# Ladder_ATTN.net
KiCad netlist of a schematic drawn in Altium Designer
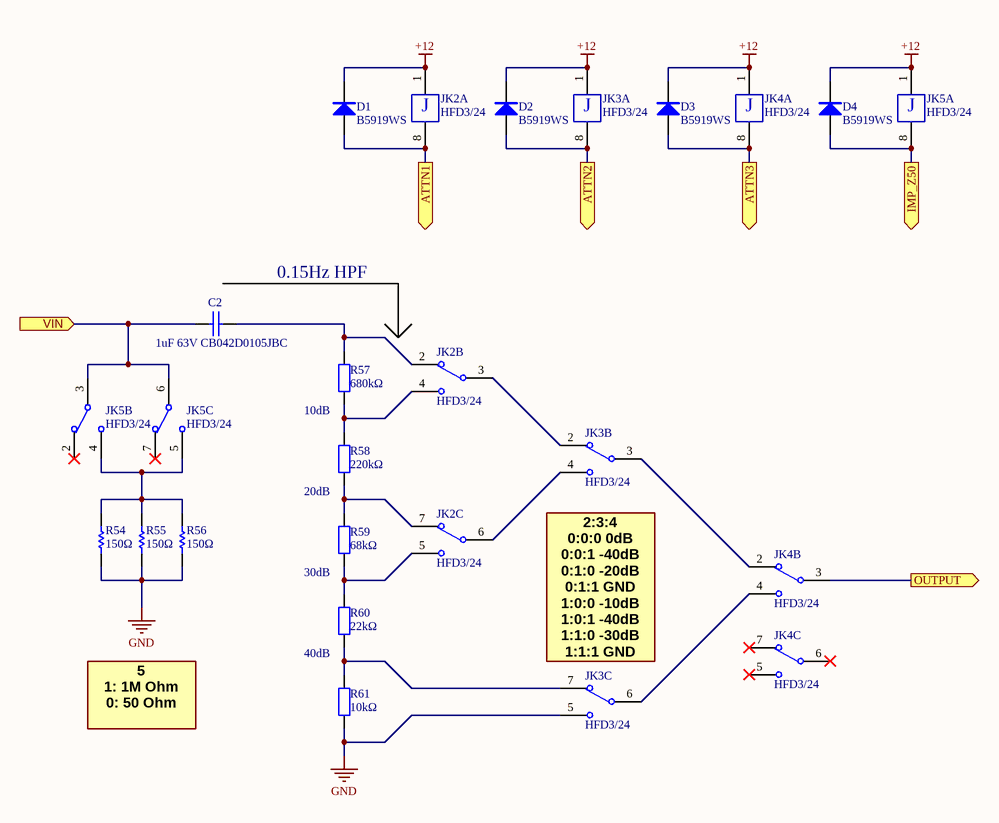
[diagram p0: Ladder_ATTN.SchDoc]

(export (version "E")
  (design (tool "Eeschema 10.0.6"))
  (components
    (comp (ref "C2")
      (value "1uF 63V CB042D0105JBC")
      (footprint "2225C")
      (description "无极性电容")
      (libsource (lib "电容") (part "CAP"))
    )
    (comp (ref "D1")
      (value "B5919WS")
      (footprint "SOD-323")
      (description "肖特基二极管")
      (fields (field (name "版权归属") "源创客"))
      (libsource (lib "源创客") (part "1N5819"))
    )
    (comp (ref "D2")
      (value "B5919WS")
      (footprint "SOD-323")
      (description "肖特基二极管")
      (fields (field (name "版权归属") "源创客"))
      (libsource (lib "源创客") (part "1N5819"))
    )
    (comp (ref "D3")
      (value "B5919WS")
      (footprint "SOD-323")
      (description "肖特基二极管")
      (fields (field (name "版权归属") "源创客"))
      (libsource (lib "源创客") (part "1N5819"))
    )
    (comp (ref "D4")
      (value "B5919WS")
      (footprint "SOD-323")
      (description "肖特基二极管")
      (fields (field (name "版权归属") "源创客"))
      (libsource (lib "源创客") (part "1N5819"))
    )
    (comp (ref "JK2")
      (value "HFD3/24")
      (footprint "HFD3-DIP")
      (description "超小型两组转换")
      (fields (field (name "版权归属") "源创客"))
      (libsource (lib "") (part "HFD3_1"))
    )
    (comp (ref "JK3")
      (value "HFD3/24")
      (footprint "HFD3-DIP")
      (description "超小型两组转换")
      (fields (field (name "版权归属") "源创客"))
      (libsource (lib "") (part "HFD3_2"))
    )
    (comp (ref "JK4")
      (value "HFD3/24")
      (footprint "HFD3-DIP")
      (description "超小型两组转换")
      (fields (field (name "版权归属") "源创客"))
      (libsource (lib "继电器") (part "HFD3"))
    )
    (comp (ref "JK5")
      (value "HFD3/24")
      (footprint "HFD3-DIP")
      (description "超小型两组转换")
      (fields (field (name "版权归属") "源创客"))
      (libsource (lib "") (part "HFD3_4"))
    )
    (comp (ref "R54") (value "150Ω") (footprint "2512R") (libsource (lib "电阻") (part "RES")))
    (comp (ref "R55") (value "150Ω") (footprint "2512R") (libsource (lib "电阻") (part "RES")))
    (comp (ref "R56") (value "150Ω") (footprint "2512R") (libsource (lib "电阻") (part "RES")))
    (comp (ref "R57")
      (value "680kΩ")
      (footprint "0603_R")
      (description "贴片电阻")
      (libsource (lib "Miscellaneous Devices LC") (part "0603 680KΩ (6803) 1%"))
    )
    (comp (ref "R58")
      (value "220kΩ")
      (footprint "0603_R")
      (description "贴片电阻")
      (libsource (lib "Miscellaneous Devices LC") (part "0603 220KΩ (2203) 1%"))
    )
    (comp (ref "R59")
      (value "68kΩ")
      (footprint "0603_R")
      (description "贴片电阻")
      (libsource (lib "Miscellaneous Devices LC") (part "0603 680KΩ (6803) 1%"))
    )
    (comp (ref "R60")
      (value "22kΩ")
      (footprint "0603_R")
      (description "贴片电阻")
      (libsource (lib "Miscellaneous Devices LC") (part "0603 220KΩ (2203) 1%"))
    )
    (comp (ref "R61")
      (value "10kΩ")
      (footprint "0603_R")
      (description "贴片电阻")
      (libsource (lib "Miscellaneous Devices LC") (part "0603 220KΩ (2203) 1%"))
    )
  )
  (nets
    (net (code "1") (name "+12") (class "Default")
      (node (ref "D1") (pin "2") (pinfunction "K_2") (pintype "passive"))
      (node (ref "D2") (pin "2") (pinfunction "K_2") (pintype "passive"))
      (node (ref "D3") (pin "2") (pinfunction "K_2") (pintype "passive"))
      (node (ref "D4") (pin "2") (pinfunction "K_2") (pintype "passive"))
      (node (ref "JK2") (pin "1") (pinfunction "1_1") (pintype "passive"))
      (node (ref "JK3") (pin "1") (pinfunction "1_1") (pintype "passive"))
      (node (ref "JK4") (pin "1") (pinfunction "1_1") (pintype "passive"))
      (node (ref "JK5") (pin "1") (pinfunction "1_1") (pintype "passive"))
    )
    (net (code "2") (name "/ATTN1") (class "Default")
      (node (ref "D1") (pin "1") (pinfunction "A_1") (pintype "passive"))
      (node (ref "JK2") (pin "8") (pinfunction "8_8") (pintype "passive"))
    )
    (net (code "3") (name "/ATTN2") (class "Default")
      (node (ref "D2") (pin "1") (pinfunction "A_1") (pintype "passive"))
      (node (ref "JK3") (pin "8") (pinfunction "8_8") (pintype "passive"))
    )
    (net (code "4") (name "/ATTN3") (class "Default")
      (node (ref "D3") (pin "1") (pinfunction "A_1") (pintype "passive"))
      (node (ref "JK4") (pin "8") (pinfunction "8_8") (pintype "passive"))
    )
    (net (code "5") (name "/IMP_Z50") (class "Default")
      (node (ref "D4") (pin "1") (pinfunction "A_1") (pintype "passive"))
      (node (ref "JK5") (pin "8") (pinfunction "8_8") (pintype "passive"))
    )
    (net (code "6") (name "/OUTPUT") (class "Default")
      (node (ref "JK4") (pin "3") (pinfunction "3_3") (pintype "passive"))
    )
    (net (code "7") (name "/VIN") (class "Default")
      (node (ref "C2") (pin "1") (pinfunction "1_1") (pintype "passive"))
      (node (ref "JK5") (pin "3") (pinfunction "3_3") (pintype "passive"))
      (node (ref "JK5") (pin "6") (pinfunction "6_6") (pintype "passive"))
    )
    (net (code "8") (name "GND") (class "Default")
      (node (ref "JK3") (pin "5") (pinfunction "5_5") (pintype "passive"))
      (node (ref "R54") (pin "1") (pinfunction "1_1") (pintype "passive"))
      (node (ref "R55") (pin "1") (pinfunction "1_1") (pintype "passive"))
      (node (ref "R56") (pin "1") (pinfunction "1_1") (pintype "passive"))
      (node (ref "R61") (pin "1") (pinfunction "1_1") (pintype "passive"))
    )
    (net (code "9") (name "Net-(C2-Pad2)") (class "Default")
      (node (ref "C2") (pin "2") (pinfunction "2_2") (pintype "passive"))
      (node (ref "JK2") (pin "2") (pinfunction "2_2") (pintype "passive"))
      (node (ref "R57") (pin "2") (pinfunction "2_2") (pintype "passive"))
    )
    (net (code "10") (name "Net-(JK2-Pad3)") (class "Default")
      (node (ref "JK2") (pin "3") (pinfunction "3_3") (pintype "passive"))
      (node (ref "JK3") (pin "2") (pinfunction "2_2") (pintype "passive"))
    )
    (net (code "11") (name "Net-(JK2-Pad4)") (class "Default")
      (node (ref "JK2") (pin "4") (pinfunction "4_4") (pintype "passive"))
      (node (ref "R57") (pin "1") (pinfunction "1_1") (pintype "passive"))
      (node (ref "R58") (pin "2") (pinfunction "2_2") (pintype "passive"))
    )
    (net (code "12") (name "Net-(JK2-Pad5)") (class "Default")
      (node (ref "JK2") (pin "5") (pinfunction "5_5") (pintype "passive"))
      (node (ref "R59") (pin "1") (pinfunction "1_1") (pintype "passive"))
      (node (ref "R60") (pin "2") (pinfunction "2_2") (pintype "passive"))
    )
    (net (code "13") (name "Net-(JK2-Pad6)") (class "Default")
      (node (ref "JK2") (pin "6") (pinfunction "6_6") (pintype "passive"))
      (node (ref "JK3") (pin "4") (pinfunction "4_4") (pintype "passive"))
    )
    (net (code "14") (name "Net-(JK2-Pad7)") (class "Default")
      (node (ref "JK2") (pin "7") (pinfunction "7_7") (pintype "passive"))
      (node (ref "R58") (pin "1") (pinfunction "1_1") (pintype "passive"))
      (node (ref "R59") (pin "2") (pinfunction "2_2") (pintype "passive"))
    )
    (net (code "15") (name "Net-(JK3-Pad3)") (class "Default")
      (node (ref "JK3") (pin "3") (pinfunction "3_3") (pintype "passive"))
      (node (ref "JK4") (pin "2") (pinfunction "2_2") (pintype "passive"))
    )
    (net (code "16") (name "Net-(JK3-Pad6)") (class "Default")
      (node (ref "JK3") (pin "6") (pinfunction "6_6") (pintype "passive"))
      (node (ref "JK4") (pin "4") (pinfunction "4_4") (pintype "passive"))
    )
    (net (code "17") (name "Net-(JK3-Pad7)") (class "Default")
      (node (ref "JK3") (pin "7") (pinfunction "7_7") (pintype "passive"))
      (node (ref "R60") (pin "1") (pinfunction "1_1") (pintype "passive"))
      (node (ref "R61") (pin "2") (pinfunction "2_2") (pintype "passive"))
    )
    (net (code "18") (name "Net-(JK5-Pad4)") (class "Default")
      (node (ref "JK5") (pin "4") (pinfunction "4_4") (pintype "passive"))
      (node (ref "JK5") (pin "5") (pinfunction "5_5") (pintype "passive"))
      (node (ref "R54") (pin "2") (pinfunction "2_2") (pintype "passive"))
      (node (ref "R55") (pin "2") (pinfunction "2_2") (pintype "passive"))
      (node (ref "R56") (pin "2") (pinfunction "2_2") (pintype "passive"))
    )
    (net (code "19") (name "unconnected-(JK4-Pad5)") (class "Default")
      (node (ref "JK4") (pin "5") (pinfunction "5_5") (pintype "passive+no_connect"))
    )
    (net (code "20") (name "unconnected-(JK4-Pad6)") (class "Default")
      (node (ref "JK4") (pin "6") (pinfunction "6_6") (pintype "passive+no_connect"))
    )
    (net (code "21") (name "unconnected-(JK4-Pad7)") (class "Default")
      (node (ref "JK4") (pin "7") (pinfunction "7_7") (pintype "passive+no_connect"))
    )
    (net (code "22") (name "unconnected-(JK5-Pad2)") (class "Default")
      (node (ref "JK5") (pin "2") (pinfunction "2_2") (pintype "passive+no_connect"))
    )
    (net (code "23") (name "unconnected-(JK5-Pad7)") (class "Default")
      (node (ref "JK5") (pin "7") (pinfunction "7_7") (pintype "passive+no_connect"))
    )
  )
)
